# Electronic_load_1_0.net
KiCad netlist of a schematic drawn in Altium Designer
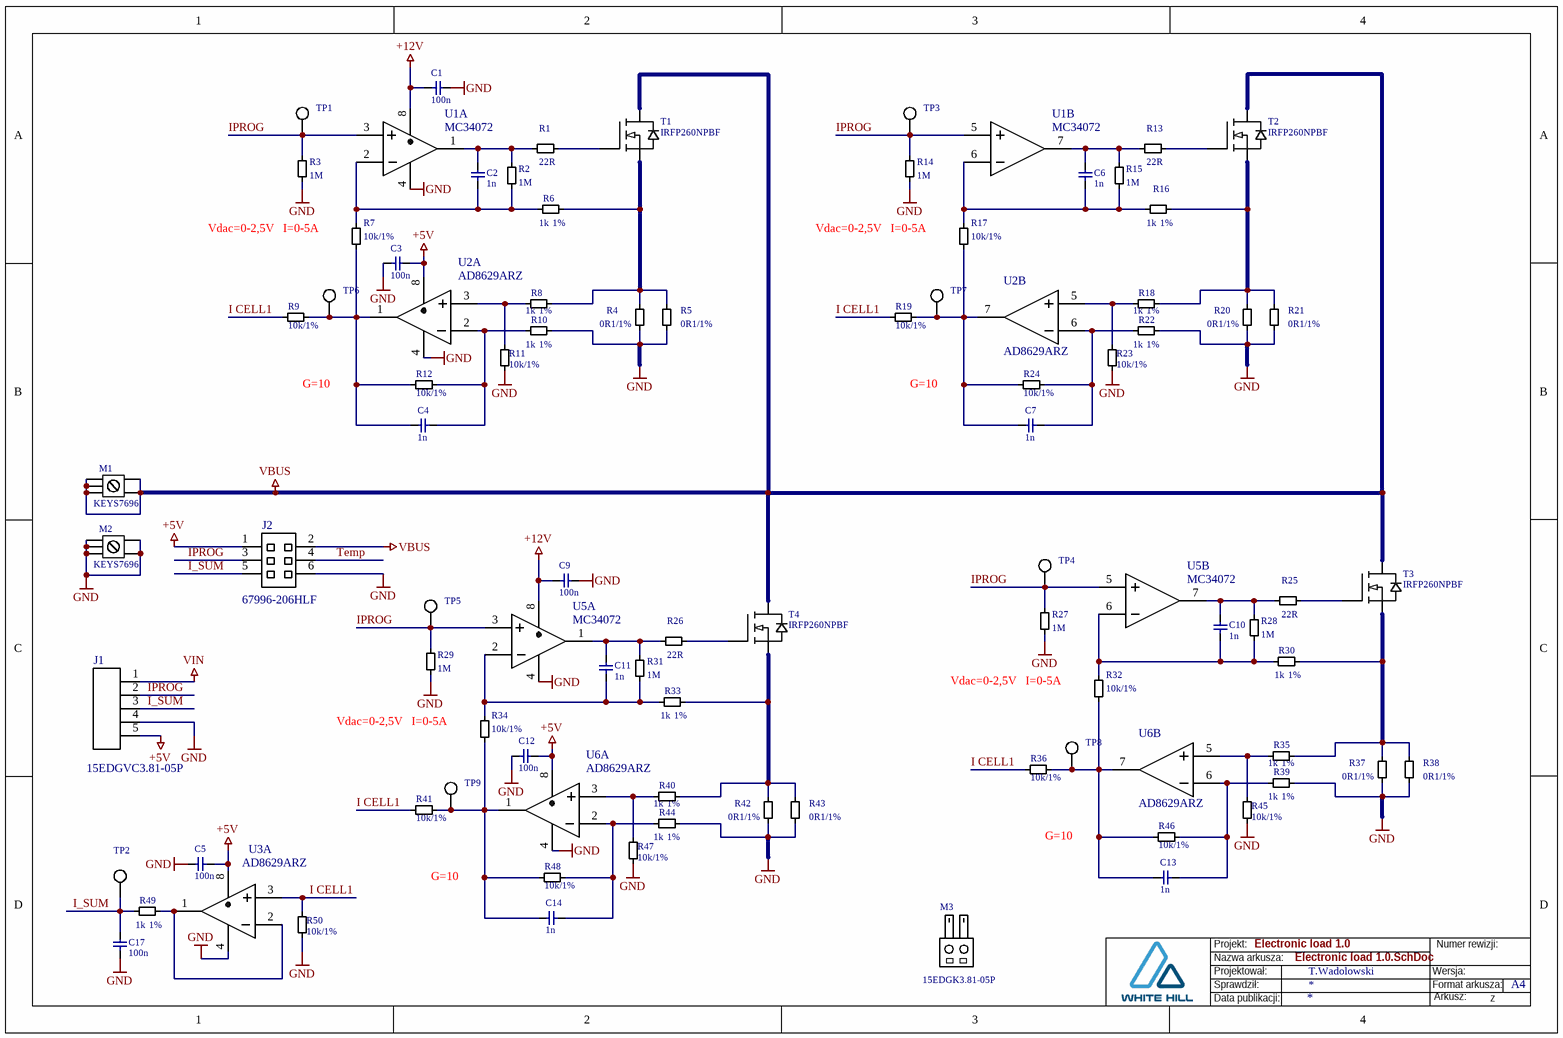
[diagram p0: Electronic load 1.0.SchDoc]

(export (version "E")
  (design (tool "Eeschema 10.0.6"))
  (components
    (comp (ref "C1")
      (value "100n")
      (footprint "C0603")
      (description "Capacitor: ceramic; 100nF; 50V; X7R; ±10%; SMD; 0603; Series: GRM")
      (fields (field (name "MANUFACTURER") "Murata") (field (name "PART NUMBER") "GRM188R71H104KA93D"))
      (libsource (lib "CAPcer") (part "C-013"))
    )
    (comp (ref "C2")
      (value "1n")
      (footprint "C0603")
      (description "Capacitor: ceramic; MLCC; 1nF; 50V; X7R; ±10%; SMD; 0603")
      (fields (field (name "MANUFACTURER") "Vishay") (field (name "PART NUMBER") "VJ0603Y102KXACW1BC"))
      (libsource (lib "CAPcer") (part "C-006"))
    )
    (comp (ref "C3")
      (value "100n")
      (footprint "C0603")
      (description "Capacitor: ceramic; 100nF; 50V; X7R; ±10%; SMD; 0603; Series: GRM")
      (fields (field (name "MANUFACTURER") "Murata") (field (name "PART NUMBER") "GRM188R71H104KA93D"))
      (libsource (lib "CAPcer") (part "C-013"))
    )
    (comp (ref "C4")
      (value "1n")
      (footprint "C0603")
      (description "Capacitor: ceramic; MLCC; 1nF; 50V; X7R; ±10%; SMD; 0603")
      (fields (field (name "MANUFACTURER") "Vishay") (field (name "PART NUMBER") "VJ0603Y102KXACW1BC"))
      (libsource (lib "CAPcer") (part "C-006"))
    )
    (comp (ref "C5")
      (value "100n")
      (footprint "C0603")
      (description "Capacitor: ceramic; 100nF; 50V; X7R; ±10%; SMD; 0603; Series: GRM")
      (fields (field (name "MANUFACTURER") "Murata") (field (name "PART NUMBER") "GRM188R71H104KA93D"))
      (libsource (lib "CAPcer") (part "C-013"))
    )
    (comp (ref "C6")
      (value "1n")
      (footprint "C0603")
      (description "Capacitor: ceramic; MLCC; 1nF; 50V; X7R; ±10%; SMD; 0603")
      (fields (field (name "MANUFACTURER") "Vishay") (field (name "PART NUMBER") "VJ0603Y102KXACW1BC"))
      (libsource (lib "CAPcer") (part "C-006"))
    )
    (comp (ref "C7")
      (value "1n")
      (footprint "C0603")
      (description "Capacitor: ceramic; MLCC; 1nF; 50V; X7R; ±10%; SMD; 0603")
      (fields (field (name "MANUFACTURER") "Vishay") (field (name "PART NUMBER") "VJ0603Y102KXACW1BC"))
      (libsource (lib "CAPcer") (part "C-006"))
    )
    (comp (ref "C9")
      (value "100n")
      (footprint "C0603")
      (description "Capacitor: ceramic; 100nF; 50V; X7R; ±10%; SMD; 0603; Series: GRM")
      (fields (field (name "MANUFACTURER") "Murata") (field (name "PART NUMBER") "GRM188R71H104KA93D"))
      (libsource (lib "CAPcer") (part "C-013"))
    )
    (comp (ref "C10")
      (value "1n")
      (footprint "C0603")
      (description "Capacitor: ceramic; MLCC; 1nF; 50V; X7R; ±10%; SMD; 0603")
      (fields (field (name "MANUFACTURER") "Vishay") (field (name "PART NUMBER") "VJ0603Y102KXACW1BC"))
      (libsource (lib "CAPcer") (part "C-006"))
    )
    (comp (ref "C11")
      (value "1n")
      (footprint "C0603")
      (description "Capacitor: ceramic; MLCC; 1nF; 50V; X7R; ±10%; SMD; 0603")
      (fields (field (name "MANUFACTURER") "Vishay") (field (name "PART NUMBER") "VJ0603Y102KXACW1BC"))
      (libsource (lib "CAPcer") (part "C-006"))
    )
    (comp (ref "C12")
      (value "100n")
      (footprint "C0603")
      (description "Capacitor: ceramic; 100nF; 50V; X7R; ±10%; SMD; 0603; Series: GRM")
      (fields (field (name "MANUFACTURER") "Murata") (field (name "PART NUMBER") "GRM188R71H104KA93D"))
      (libsource (lib "CAPcer") (part "C-013"))
    )
    (comp (ref "C13")
      (value "1n")
      (footprint "C0603")
      (description "Capacitor: ceramic; MLCC; 1nF; 50V; X7R; ±10%; SMD; 0603")
      (fields (field (name "MANUFACTURER") "Vishay") (field (name "PART NUMBER") "VJ0603Y102KXACW1BC"))
      (libsource (lib "CAPcer") (part "C-006"))
    )
    (comp (ref "C14")
      (value "1n")
      (footprint "C0603")
      (description "Capacitor: ceramic; MLCC; 1nF; 50V; X7R; ±10%; SMD; 0603")
      (fields (field (name "MANUFACTURER") "Vishay") (field (name "PART NUMBER") "VJ0603Y102KXACW1BC"))
      (libsource (lib "CAPcer") (part "C-006"))
    )
    (comp (ref "C17")
      (value "100n")
      (footprint "C0603")
      (description "Capacitor: ceramic; 100nF; 50V; X7R; ±10%; SMD; 0603; Series: GRM")
      (fields (field (name "MANUFACTURER") "Murata") (field (name "PART NUMBER") "GRM188R71H104KA93D"))
      (libsource (lib "CAPcer") (part "C-013"))
    )
    (comp (ref "J1")
      (value "15EDGVC3.81-05P")
      (footprint "MCV1,5/5-G3,81")
      (description "Pluggable terminal block; 3.81mm; ways:5; straight; socket; male")
      (fields (field (name "PART NUMBER") "15EDGVC-3.81-05P-14-00A(H)"))
      (libsource (lib "WH") (part "CON5"))
    )
    (comp (ref "J2")
      (value "67996-206HLF")
      (footprint "GP2x3")
      (description "Pin header; pin strips; male;2.54mm; PIN:6; THT")
      (fields (field (name "MANUFACTURER") "Amphenol"))
      (libsource (lib "WH") (part "CON2x3"))
    )
    (comp (ref "M1")
      (value "KEYS7696")
      (footprint "KEY-7696")
      (description "Terminal: screw terminal; THT, screw terminal; silver; 7x5mm")
      (fields (field (name "MANUFACTURER") "Keystone") (field (name "PART NUMBER") "7696"))
      (libsource (lib "WH") (part "M3 pcb"))
    )
    (comp (ref "M2")
      (value "KEYS7696")
      (footprint "KEY-7696")
      (description "Terminal: screw terminal; THT, screw terminal; silver; 7x5mm")
      (fields (field (name "MANUFACTURER") "Keystone") (field (name "PART NUMBER") "7696"))
      (libsource (lib "WH") (part "M3 pcb"))
    )
    (comp (ref "M3")
      (value "15EDGK3.81-05P")
      (description "Pluggable terminal block; 3.81mm; ways:5; straight; plug; female")
      (fields (field (name "PART NUMBER") "15EDGK-3.81-05P-14-00A(H)"))
      (libsource (lib "WH") (part "Wtyk 3,81"))
    )
    (comp (ref "R1")
      (value "22R")
      (footprint "R0603")
      (description "Resistor: thick film; SMD; 0603; 22R; 0.1W; ±5%;")
      (fields (field (name "MANUFACTURER") "Royal Ohm") (field (name "PART NUMBER") "0603SAJ0220T5E"))
      (libsource (lib "Resistors") (part "R-002"))
    )
    (comp (ref "R2")
      (value "1M")
      (footprint "R0603")
      (description "Resistor: thick film; SMD; 0603; 1M; 0.1W; ±5%;")
      (fields (field (name "MANUFACTURER") "Royal Ohm") (field (name "PART NUMBER") "0603SAJ0105T5E"))
      (libsource (lib "Resistors") (part "R-022"))
    )
    (comp (ref "R3")
      (value "1M")
      (footprint "R0603")
      (description "Resistor: thick film; SMD; 0603; 1M; 0.1W; ±5%;")
      (fields (field (name "MANUFACTURER") "Royal Ohm") (field (name "PART NUMBER") "0603SAJ0105T5E"))
      (libsource (lib "Resistors") (part "R-022"))
    )
    (comp (ref "R4")
      (value "0R1/1%")
      (footprint "R2512")
      (description "Rezystor: pomiarowy; SMD; 2512; 100mOhm; 3W; ±1%; 50ppm")
      (fields (field (name "MANUFACTURER") "Viking") (field (name "PART NUMBER") "LPR12FTDRR100"))
      (libsource (lib "") (part "R_2"))
    )
    (comp (ref "R5")
      (value "0R1/1%")
      (footprint "R2512")
      (description "Rezystor: pomiarowy; SMD; 2512; 100mOhm; 3W; ±1%; 50ppm")
      (fields (field (name "MANUFACTURER") "Viking") (field (name "PART NUMBER") "LPR12FTDRR100"))
      (libsource (lib "") (part "R_2"))
    )
    (comp (ref "R6")
      (value "1k")
      (footprint "R0603")
      (description "Resistor: thick film; SMD; 0603; 1k; 0.1W; ±1%")
      (fields
        (field (name "MANUFACTURER") "Royal Ohm")
        (field (name "PART NUMBER") "0603SAF1001T5E")
        (field (name "TOLERANCE") "1%")
      )
      (libsource (lib "Resistors") (part "R-035"))
    )
    (comp (ref "R7")
      (value "10k/1%")
      (footprint "R0603")
      (description "Rezystor: thick film; SMD; 0603; 10kOhm; 0,1W; ±1%; -55÷155°C")
      (fields (field (name "MANUFACTURER") "VISHAY") (field (name "PART NUMBER") "CRCW060310K0FKTABC"))
      (libsource (lib "DGI") (part "R"))
    )
    (comp (ref "R8")
      (value "1k")
      (footprint "R0603")
      (description "Resistor: thick film; SMD; 0603; 1k; 0.1W; ±1%")
      (fields
        (field (name "MANUFACTURER") "Royal Ohm")
        (field (name "PART NUMBER") "0603SAF1001T5E")
        (field (name "TOLERANCE") "1%")
      )
      (libsource (lib "Resistors") (part "R-035"))
    )
    (comp (ref "R9")
      (value "10k/1%")
      (footprint "R0603")
      (description "Rezystor: thick film; SMD; 0603; 10kOhm; 0,1W; ±1%; -55÷155°C")
      (fields (field (name "MANUFACTURER") "VISHAY") (field (name "PART NUMBER") "CRCW060310K0FKTABC"))
      (libsource (lib "") (part "R_1"))
    )
    (comp (ref "R10")
      (value "1k")
      (footprint "R0603")
      (description "Resistor: thick film; SMD; 0603; 1k; 0.1W; ±1%")
      (fields
        (field (name "MANUFACTURER") "Royal Ohm")
        (field (name "PART NUMBER") "0603SAF1001T5E")
        (field (name "TOLERANCE") "1%")
      )
      (libsource (lib "Resistors") (part "R-035"))
    )
    (comp (ref "R11")
      (value "10k/1%")
      (footprint "R0603")
      (description "Rezystor: thick film; SMD; 0603; 10kOhm; 0,1W; ±1%; -55÷155°C")
      (fields (field (name "MANUFACTURER") "VISHAY") (field (name "PART NUMBER") "CRCW060310K0FKTABC"))
      (libsource (lib "") (part "R_2"))
    )
    (comp (ref "R12")
      (value "10k/1%")
      (footprint "R0603")
      (description "Rezystor: thick film; SMD; 0603; 10kOhm; 0,1W; ±1%; -55÷155°C")
      (fields (field (name "MANUFACTURER") "VISHAY") (field (name "PART NUMBER") "CRCW060310K0FKTABC"))
      (libsource (lib "") (part "R_3"))
    )
    (comp (ref "R13")
      (value "22R")
      (footprint "R0603")
      (description "Resistor: thick film; SMD; 0603; 22R; 0.1W; ±5%;")
      (fields (field (name "MANUFACTURER") "Royal Ohm") (field (name "PART NUMBER") "0603SAJ0220T5E"))
      (libsource (lib "Resistors") (part "R-002"))
    )
    (comp (ref "R14")
      (value "1M")
      (footprint "R0603")
      (description "Resistor: thick film; SMD; 0603; 1M; 0.1W; ±5%;")
      (fields (field (name "MANUFACTURER") "Royal Ohm") (field (name "PART NUMBER") "0603SAJ0105T5E"))
      (libsource (lib "Resistors") (part "R-022"))
    )
    (comp (ref "R15")
      (value "1M")
      (footprint "R0603")
      (description "Resistor: thick film; SMD; 0603; 1M; 0.1W; ±5%;")
      (fields (field (name "MANUFACTURER") "Royal Ohm") (field (name "PART NUMBER") "0603SAJ0105T5E"))
      (libsource (lib "Resistors") (part "R-022"))
    )
    (comp (ref "R16")
      (value "1k")
      (footprint "R0603")
      (description "Resistor: thick film; SMD; 0603; 1k; 0.1W; ±1%")
      (fields
        (field (name "MANUFACTURER") "Royal Ohm")
        (field (name "PART NUMBER") "0603SAF1001T5E")
        (field (name "TOLERANCE") "1%")
      )
      (libsource (lib "Resistors") (part "R-035"))
    )
    (comp (ref "R17")
      (value "10k/1%")
      (footprint "R0603")
      (description "Rezystor: thick film; SMD; 0603; 10kOhm; 0,1W; ±1%; -55÷155°C")
      (fields (field (name "MANUFACTURER") "VISHAY") (field (name "PART NUMBER") "CRCW060310K0FKTABC"))
      (libsource (lib "DGI") (part "R"))
    )
    (comp (ref "R18")
      (value "1k")
      (footprint "R0603")
      (description "Resistor: thick film; SMD; 0603; 1k; 0.1W; ±1%")
      (fields
        (field (name "MANUFACTURER") "Royal Ohm")
        (field (name "PART NUMBER") "0603SAF1001T5E")
        (field (name "TOLERANCE") "1%")
      )
      (libsource (lib "Resistors") (part "R-035"))
    )
    (comp (ref "R19")
      (value "10k/1%")
      (footprint "R0603")
      (description "Rezystor: thick film; SMD; 0603; 10kOhm; 0,1W; ±1%; -55÷155°C")
      (fields (field (name "MANUFACTURER") "VISHAY") (field (name "PART NUMBER") "CRCW060310K0FKTABC"))
      (libsource (lib "") (part "R_1"))
    )
    (comp (ref "R20")
      (value "0R1/1%")
      (footprint "R2512")
      (description "Rezystor: pomiarowy; SMD; 2512; 100mOhm; 3W; ±1%; 50ppm")
      (fields (field (name "MANUFACTURER") "Viking") (field (name "PART NUMBER") "LPR12FTDRR100"))
      (libsource (lib "") (part "R_2"))
    )
    (comp (ref "R21")
      (value "0R1/1%")
      (footprint "R2512")
      (description "Rezystor: pomiarowy; SMD; 2512; 100mOhm; 3W; ±1%; 50ppm")
      (fields (field (name "MANUFACTURER") "Viking") (field (name "PART NUMBER") "LPR12FTDRR100"))
      (libsource (lib "") (part "R_2"))
    )
    (comp (ref "R22")
      (value "1k")
      (footprint "R0603")
      (description "Resistor: thick film; SMD; 0603; 1k; 0.1W; ±1%")
      (fields
        (field (name "MANUFACTURER") "Royal Ohm")
        (field (name "PART NUMBER") "0603SAF1001T5E")
        (field (name "TOLERANCE") "1%")
      )
      (libsource (lib "Resistors") (part "R-035"))
    )
    (comp (ref "R23")
      (value "10k/1%")
      (footprint "R0603")
      (description "Rezystor: thick film; SMD; 0603; 10kOhm; 0,1W; ±1%; -55÷155°C")
      (fields (field (name "MANUFACTURER") "VISHAY") (field (name "PART NUMBER") "CRCW060310K0FKTABC"))
      (libsource (lib "") (part "R_2"))
    )
    (comp (ref "R24")
      (value "10k/1%")
      (footprint "R0603")
      (description "Rezystor: thick film; SMD; 0603; 10kOhm; 0,1W; ±1%; -55÷155°C")
      (fields (field (name "MANUFACTURER") "VISHAY") (field (name "PART NUMBER") "CRCW060310K0FKTABC"))
      (libsource (lib "") (part "R_3"))
    )
    (comp (ref "R25")
      (value "22R")
      (footprint "R0603")
      (description "Resistor: thick film; SMD; 0603; 22R; 0.1W; ±5%;")
      (fields (field (name "MANUFACTURER") "Royal Ohm") (field (name "PART NUMBER") "0603SAJ0220T5E"))
      (libsource (lib "Resistors") (part "R-002"))
    )
    (comp (ref "R26")
      (value "22R")
      (footprint "R0603")
      (description "Resistor: thick film; SMD; 0603; 22R; 0.1W; ±5%;")
      (fields (field (name "MANUFACTURER") "Royal Ohm") (field (name "PART NUMBER") "0603SAJ0220T5E"))
      (libsource (lib "Resistors") (part "R-002"))
    )
    (comp (ref "R27")
      (value "1M")
      (footprint "R0603")
      (description "Resistor: thick film; SMD; 0603; 1M; 0.1W; ±5%;")
      (fields (field (name "MANUFACTURER") "Royal Ohm") (field (name "PART NUMBER") "0603SAJ0105T5E"))
      (libsource (lib "Resistors") (part "R-022"))
    )
    (comp (ref "R28")
      (value "1M")
      (footprint "R0603")
      (description "Resistor: thick film; SMD; 0603; 1M; 0.1W; ±5%;")
      (fields (field (name "MANUFACTURER") "Royal Ohm") (field (name "PART NUMBER") "0603SAJ0105T5E"))
      (libsource (lib "Resistors") (part "R-022"))
    )
    (comp (ref "R29")
      (value "1M")
      (footprint "R0603")
      (description "Resistor: thick film; SMD; 0603; 1M; 0.1W; ±5%;")
      (fields (field (name "MANUFACTURER") "Royal Ohm") (field (name "PART NUMBER") "0603SAJ0105T5E"))
      (libsource (lib "Resistors") (part "R-022"))
    )
    (comp (ref "R30")
      (value "1k")
      (footprint "R0603")
      (description "Resistor: thick film; SMD; 0603; 1k; 0.1W; ±1%")
      (fields
        (field (name "MANUFACTURER") "Royal Ohm")
        (field (name "PART NUMBER") "0603SAF1001T5E")
        (field (name "TOLERANCE") "1%")
      )
      (libsource (lib "Resistors") (part "R-035"))
    )
    (comp (ref "R31")
      (value "1M")
      (footprint "R0603")
      (description "Resistor: thick film; SMD; 0603; 1M; 0.1W; ±5%;")
      (fields (field (name "MANUFACTURER") "Royal Ohm") (field (name "PART NUMBER") "0603SAJ0105T5E"))
      (libsource (lib "Resistors") (part "R-022"))
    )
    (comp (ref "R32")
      (value "10k/1%")
      (footprint "R0603")
      (description "Rezystor: thick film; SMD; 0603; 10kOhm; 0,1W; ±1%; -55÷155°C")
      (fields (field (name "MANUFACTURER") "VISHAY") (field (name "PART NUMBER") "CRCW060310K0FKTABC"))
      (libsource (lib "DGI") (part "R"))
    )
    (comp (ref "R33")
      (value "1k")
      (footprint "R0603")
      (description "Resistor: thick film; SMD; 0603; 1k; 0.1W; ±1%")
      (fields
        (field (name "MANUFACTURER") "Royal Ohm")
        (field (name "PART NUMBER") "0603SAF1001T5E")
        (field (name "TOLERANCE") "1%")
      )
      (libsource (lib "Resistors") (part "R-035"))
    )
    (comp (ref "R34")
      (value "10k/1%")
      (footprint "R0603")
      (description "Rezystor: thick film; SMD; 0603; 10kOhm; 0,1W; ±1%; -55÷155°C")
      (fields (field (name "MANUFACTURER") "VISHAY") (field (name "PART NUMBER") "CRCW060310K0FKTABC"))
      (libsource (lib "DGI") (part "R"))
    )
    (comp (ref "R35")
      (value "1k")
      (footprint "R0603")
      (description "Resistor: thick film; SMD; 0603; 1k; 0.1W; ±1%")
      (fields
        (field (name "MANUFACTURER") "Royal Ohm")
        (field (name "PART NUMBER") "0603SAF1001T5E")
        (field (name "TOLERANCE") "1%")
      )
      (libsource (lib "Resistors") (part "R-035"))
    )
    (comp (ref "R36")
      (value "10k/1%")
      (footprint "R0603")
      (description "Rezystor: thick film; SMD; 0603; 10kOhm; 0,1W; ±1%; -55÷155°C")
      (fields (field (name "MANUFACTURER") "VISHAY") (field (name "PART NUMBER") "CRCW060310K0FKTABC"))
      (libsource (lib "") (part "R_1"))
    )
    (comp (ref "R37")
      (value "0R1/1%")
      (footprint "R2512")
      (description "Rezystor: pomiarowy; SMD; 2512; 100mOhm; 3W; ±1%; 50ppm")
      (fields (field (name "MANUFACTURER") "Viking") (field (name "PART NUMBER") "LPR12FTDRR100"))
      (libsource (lib "") (part "R_2"))
    )
    (comp (ref "R38")
      (value "0R1/1%")
      (footprint "R2512")
      (description "Rezystor: pomiarowy; SMD; 2512; 100mOhm; 3W; ±1%; 50ppm")
      (fields (field (name "MANUFACTURER") "Viking") (field (name "PART NUMBER") "LPR12FTDRR100"))
      (libsource (lib "") (part "R_2"))
    )
    (comp (ref "R39")
      (value "1k")
      (footprint "R0603")
      (description "Resistor: thick film; SMD; 0603; 1k; 0.1W; ±1%")
      (fields
        (field (name "MANUFACTURER") "Royal Ohm")
        (field (name "PART NUMBER") "0603SAF1001T5E")
        (field (name "TOLERANCE") "1%")
      )
      (libsource (lib "Resistors") (part "R-035"))
    )
    (comp (ref "R40")
      (value "1k")
      (footprint "R0603")
      (description "Resistor: thick film; SMD; 0603; 1k; 0.1W; ±1%")
      (fields
        (field (name "MANUFACTURER") "Royal Ohm")
        (field (name "PART NUMBER") "0603SAF1001T5E")
        (field (name "TOLERANCE") "1%")
      )
      (libsource (lib "Resistors") (part "R-035"))
    )
    (comp (ref "R41")
      (value "10k/1%")
      (footprint "R0603")
      (description "Rezystor: thick film; SMD; 0603; 10kOhm; 0,1W; ±1%; -55÷155°C")
      (fields (field (name "MANUFACTURER") "VISHAY") (field (name "PART NUMBER") "CRCW060310K0FKTABC"))
      (libsource (lib "") (part "R_1"))
    )
    (comp (ref "R42")
      (value "0R1/1%")
      (footprint "R2512")
      (description "Rezystor: pomiarowy; SMD; 2512; 100mOhm; 3W; ±1%; 50ppm")
      (fields (field (name "MANUFACTURER") "Viking") (field (name "PART NUMBER") "LPR12FTDRR100"))
      (libsource (lib "") (part "R_2"))
    )
    (comp (ref "R43")
      (value "0R1/1%")
      (footprint "R2512")
      (description "Rezystor: pomiarowy; SMD; 2512; 100mOhm; 3W; ±1%; 50ppm")
      (fields (field (name "MANUFACTURER") "Viking") (field (name "PART NUMBER") "LPR12FTDRR100"))
      (libsource (lib "") (part "R_2"))
    )
    (comp (ref "R44")
      (value "1k")
      (footprint "R0603")
      (description "Resistor: thick film; SMD; 0603; 1k; 0.1W; ±1%")
      (fields
        (field (name "MANUFACTURER") "Royal Ohm")
        (field (name "PART NUMBER") "0603SAF1001T5E")
        (field (name "TOLERANCE") "1%")
      )
      (libsource (lib "Resistors") (part "R-035"))
    )
    (comp (ref "R45")
      (value "10k/1%")
      (footprint "R0603")
      (description "Rezystor: thick film; SMD; 0603; 10kOhm; 0,1W; ±1%; -55÷155°C")
      (fields (field (name "MANUFACTURER") "VISHAY") (field (name "PART NUMBER") "CRCW060310K0FKTABC"))
      (libsource (lib "") (part "R_2"))
    )
    (comp (ref "R46")
      (value "10k/1%")
      (footprint "R0603")
      (description "Rezystor: thick film; SMD; 0603; 10kOhm; 0,1W; ±1%; -55÷155°C")
      (fields (field (name "MANUFACTURER") "VISHAY") (field (name "PART NUMBER") "CRCW060310K0FKTABC"))
      (libsource (lib "") (part "R_3"))
    )
    (comp (ref "R47")
      (value "10k/1%")
      (footprint "R0603")
      (description "Rezystor: thick film; SMD; 0603; 10kOhm; 0,1W; ±1%; -55÷155°C")
      (fields (field (name "MANUFACTURER") "VISHAY") (field (name "PART NUMBER") "CRCW060310K0FKTABC"))
      (libsource (lib "") (part "R_2"))
    )
    (comp (ref "R48")
      (value "10k/1%")
      (footprint "R0603")
      (description "Rezystor: thick film; SMD; 0603; 10kOhm; 0,1W; ±1%; -55÷155°C")
      (fields (field (name "MANUFACTURER") "VISHAY") (field (name "PART NUMBER") "CRCW060310K0FKTABC"))
      (libsource (lib "") (part "R_3"))
    )
    (comp (ref "R49")
      (value "1k")
      (footprint "R0603")
      (description "Resistor: thick film; SMD; 0603; 1k; 0.1W; ±1%")
      (fields
        (field (name "MANUFACTURER") "Royal Ohm")
        (field (name "PART NUMBER") "0603SAF1001T5E")
        (field (name "TOLERANCE") "1%")
      )
      (libsource (lib "Resistors") (part "R-035"))
    )
    (comp (ref "R50")
      (value "10k/1%")
      (footprint "R0603")
      (description "Rezystor: thick film; SMD; 0603; 10kOhm; 0,1W; ±1%; -55÷155°C")
      (fields (field (name "MANUFACTURER") "VISHAY") (field (name "PART NUMBER") "CRCW060310K0FKTABC"))
      (libsource (lib "DGI") (part "R"))
    )
    (comp (ref "T1")
      (value "IRFP260NPBF")
      (footprint "TO-247-HOR")
      (description "Tranzystor: N-MOSFET; unipolarny; HEXFET; 200V; 35A; 300W; TO247AC")
      (fields (field (name "MANUFACTURER") "Infineon"))
      (libsource (lib "WH") (part "IRFP260NPBF"))
    )
    (comp (ref "T2")
      (value "IRFP260NPBF")
      (footprint "TO-247-HOR")
      (description "Tranzystor: N-MOSFET; unipolarny; HEXFET; 200V; 35A; 300W; TO247AC")
      (fields (field (name "MANUFACTURER") "Infineon"))
      (libsource (lib "WH") (part "IRFP260NPBF"))
    )
    (comp (ref "T3")
      (value "IRFP260NPBF")
      (footprint "TO-247-HOR")
      (description "Tranzystor: N-MOSFET; unipolarny; HEXFET; 200V; 35A; 300W; TO247AC")
      (fields (field (name "MANUFACTURER") "Infineon"))
      (libsource (lib "WH") (part "IRFP260NPBF"))
    )
    (comp (ref "T4")
      (value "IRFP260NPBF")
      (footprint "TO-247-HOR")
      (description "Tranzystor: N-MOSFET; unipolarny; HEXFET; 200V; 35A; 300W; TO247AC")
      (fields (field (name "MANUFACTURER") "Infineon"))
      (libsource (lib "WH") (part "IRFP260NPBF"))
    )
    (comp (ref "TP1")
      (value "TP")
      (footprint "TP")
      (description "Test point")
      (libsource (lib "DGI") (part "TP"))
    )
    (comp (ref "TP2")
      (value "TP")
      (footprint "TP")
      (description "Test point")
      (libsource (lib "DGI") (part "TP"))
    )
    (comp (ref "TP3")
      (value "TP")
      (footprint "TP")
      (description "Test point")
      (libsource (lib "DGI") (part "TP"))
    )
    (comp (ref "TP4")
      (value "TP")
      (footprint "TP")
      (description "Test point")
      (libsource (lib "DGI") (part "TP"))
    )
    (comp (ref "TP5")
      (value "TP")
      (footprint "TP")
      (description "Test point")
      (libsource (lib "DGI") (part "TP"))
    )
    (comp (ref "TP6")
      (value "TP")
      (footprint "TP")
      (description "Test point")
      (libsource (lib "DGI") (part "TP"))
    )
    (comp (ref "TP7")
      (value "TP")
      (footprint "TP")
      (description "Test point")
      (libsource (lib "DGI") (part "TP"))
    )
    (comp (ref "TP8")
      (value "TP")
      (footprint "TP")
      (description "Test point")
      (libsource (lib "DGI") (part "TP"))
    )
    (comp (ref "TP9")
      (value "TP")
      (footprint "TP")
      (description "Test point")
      (libsource (lib "DGI") (part "TP"))
    )
    (comp (ref "U1")
      (value "MC34072")
      (footprint "SO-8")
      (description "Operational Amplifier Dual;4,5MHz,3-44V,SOIC-8")
      (fields (field (name "MANUFACTURER") "TI") (field (name "PART NUMBER") "MC34072ADG"))
      (libsource (lib "WH") (part "MC34072"))
    )
    (comp (ref "U2")
      (value "AD8629ARZ")
      (footprint "SO-8")
      (description "Zero-Drift, Single-Supply, Rail-to-Rail  Input/Output Operational Amplifier")
      (fields (field (name "MANUFACTURER") "Analog Devices"))
      (libsource (lib "WH") (part "AD8629"))
    )
    (comp (ref "U3")
      (value "AD8629ARZ")
      (footprint "SO-8")
      (description "Zero-Drift, Single-Supply, Rail-to-Rail  Input/Output Operational Amplifier")
      (fields (field (name "MANUFACTURER") "Analog Devices"))
      (libsource (lib "WH") (part "AD8629"))
    )
    (comp (ref "U5")
      (value "MC34072")
      (footprint "SO-8")
      (description "Operational Amplifier Dual;4,5MHz,3-44V,SOIC-8")
      (fields (field (name "MANUFACTURER") "TI") (field (name "PART NUMBER") "MC34072ADG"))
      (libsource (lib "WH") (part "MC34072"))
    )
    (comp (ref "U6")
      (value "AD8629ARZ")
      (footprint "SO-8")
      (description "Zero-Drift, Single-Supply, Rail-to-Rail  Input/Output Operational Amplifier")
      (fields (field (name "MANUFACTURER") "Analog Devices"))
      (libsource (lib "WH") (part "AD8629"))
    )
  )
  (nets
    (net (code "1") (name "+5V") (class "Default")
      (node (ref "C12") (pin "1") (pinfunction "1_1") (pintype "passive"))
      (node (ref "C3") (pin "1") (pinfunction "1_1") (pintype "passive"))
      (node (ref "C5") (pin "2") (pinfunction "2_2") (pintype "passive"))
      (node (ref "J1") (pin "5") (pinfunction "5_5") (pintype "passive"))
      (node (ref "J2") (pin "1") (pinfunction "1_1") (pintype "passive"))
      (node (ref "U2") (pin "8") (pinfunction "V+_8") (pintype "passive"))
      (node (ref "U3") (pin "8") (pinfunction "V+_8") (pintype "passive"))
      (node (ref "U6") (pin "8") (pinfunction "V+_8") (pintype "passive"))
    )
    (net (code "2") (name "+12V") (class "Default")
      (node (ref "C1") (pin "2") (pinfunction "2_2") (pintype "passive"))
      (node (ref "C9") (pin "2") (pinfunction "2_2") (pintype "passive"))
      (node (ref "U1") (pin "8") (pinfunction "V+_8") (pintype "passive"))
      (node (ref "U5") (pin "8") (pinfunction "V+_8") (pintype "passive"))
    )
    (net (code "3") (name "/I CELL1") (class "Default")
      (node (ref "R19") (pin "1") (pinfunction "TOP_1") (pintype "passive"))
      (node (ref "R36") (pin "1") (pinfunction "TOP_1") (pintype "passive"))
      (node (ref "R41") (pin "1") (pinfunction "TOP_1") (pintype "passive"))
      (node (ref "R50") (pin "2") (pinfunction "BOT_2") (pintype "passive"))
      (node (ref "R9") (pin "1") (pinfunction "TOP_1") (pintype "passive"))
      (node (ref "U3") (pin "3") (pinfunction "1IN+_3") (pintype "passive"))
    )
    (net (code "4") (name "/IPROG") (class "Default")
      (node (ref "J1") (pin "2") (pinfunction "2_2") (pintype "passive"))
      (node (ref "J2") (pin "3") (pinfunction "3_3") (pintype "passive"))
      (node (ref "R14") (pin "2") (pinfunction "BOT_2") (pintype "passive"))
      (node (ref "R27") (pin "2") (pinfunction "BOT_2") (pintype "passive"))
      (node (ref "R29") (pin "2") (pinfunction "BOT_2") (pintype "passive"))
      (node (ref "R3") (pin "2") (pinfunction "BOT_2") (pintype "passive"))
      (node (ref "TP1") (pin "1") (pinfunction "1_1") (pintype "passive"))
      (node (ref "TP3") (pin "1") (pinfunction "1_1") (pintype "passive"))
      (node (ref "TP4") (pin "1") (pinfunction "1_1") (pintype "passive"))
      (node (ref "TP5") (pin "1") (pinfunction "1_1") (pintype "passive"))
      (node (ref "U1") (pin "3") (pinfunction "1IN+_3") (pintype "passive"))
      (node (ref "U1") (pin "5") (pinfunction "2IN+_5") (pintype "passive"))
      (node (ref "U5") (pin "3") (pinfunction "1IN+_3") (pintype "passive"))
      (node (ref "U5") (pin "5") (pinfunction "2IN+_5") (pintype "passive"))
    )
    (net (code "5") (name "/I_SUM") (class "Default")
      (node (ref "C17") (pin "1") (pinfunction "1_1") (pintype "passive"))
      (node (ref "J1") (pin "3") (pinfunction "3_3") (pintype "passive"))
      (node (ref "J2") (pin "5") (pinfunction "5_5") (pintype "passive"))
      (node (ref "R49") (pin "2") (pinfunction "BOT_2") (pintype "passive"))
      (node (ref "TP2") (pin "1") (pinfunction "1_1") (pintype "passive"))
    )
    (net (code "6") (name "/Temp") (class "Default")
      (node (ref "J2") (pin "4") (pinfunction "4_4") (pintype "passive"))
    )
    (net (code "7") (name "GND") (class "Default")
      (node (ref "C1") (pin "1") (pinfunction "1_1") (pintype "passive"))
      (node (ref "C12") (pin "2") (pinfunction "2_2") (pintype "passive"))
      (node (ref "C17") (pin "2") (pinfunction "2_2") (pintype "passive"))
      (node (ref "C3") (pin "2") (pinfunction "2_2") (pintype "passive"))
      (node (ref "C5") (pin "1") (pinfunction "1_1") (pintype "passive"))
      (node (ref "C9") (pin "1") (pinfunction "1_1") (pintype "passive"))
      (node (ref "J1") (pin "4") (pinfunction "4_4") (pintype "passive"))
      (node (ref "J2") (pin "6") (pinfunction "6_6") (pintype "passive"))
      (node (ref "M2") (pin "1") (pinfunction "1_1") (pintype "passive"))
      (node (ref "M2") (pin "2") (pinfunction "2_2") (pintype "passive"))
      (node (ref "M2") (pin "3") (pinfunction "3_3") (pintype "passive"))
      (node (ref "M2") (pin "4") (pinfunction "4_4") (pintype "passive"))
      (node (ref "M2") (pin "5") (pinfunction "5_5") (pintype "passive"))
      (node (ref "R10") (pin "1") (pinfunction "TOP_1") (pintype "passive"))
      (node (ref "R11") (pin "2") (pinfunction "BOT_2") (pintype "passive"))
      (node (ref "R14") (pin "1") (pinfunction "TOP_1") (pintype "passive"))
      (node (ref "R20") (pin "2") (pinfunction "BOT_2") (pintype "passive"))
      (node (ref "R21") (pin "2") (pinfunction "BOT_2") (pintype "passive"))
      (node (ref "R22") (pin "1") (pinfunction "TOP_1") (pintype "passive"))
      (node (ref "R23") (pin "2") (pinfunction "BOT_2") (pintype "passive"))
      (node (ref "R27") (pin "1") (pinfunction "TOP_1") (pintype "passive"))
      (node (ref "R29") (pin "1") (pinfunction "TOP_1") (pintype "passive"))
      (node (ref "R3") (pin "1") (pinfunction "TOP_1") (pintype "passive"))
      (node (ref "R37") (pin "2") (pinfunction "BOT_2") (pintype "passive"))
      (node (ref "R38") (pin "2") (pinfunction "BOT_2") (pintype "passive"))
      (node (ref "R39") (pin "1") (pinfunction "TOP_1") (pintype "passive"))
      (node (ref "R4") (pin "2") (pinfunction "BOT_2") (pintype "passive"))
      (node (ref "R42") (pin "2") (pinfunction "BOT_2") (pintype "passive"))
      (node (ref "R43") (pin "2") (pinfunction "BOT_2") (pintype "passive"))
      (node (ref "R44") (pin "1") (pinfunction "TOP_1") (pintype "passive"))
      (node (ref "R45") (pin "2") (pinfunction "BOT_2") (pintype "passive"))
      (node (ref "R47") (pin "2") (pinfunction "BOT_2") (pintype "passive"))
      (node (ref "R5") (pin "2") (pinfunction "BOT_2") (pintype "passive"))
      (node (ref "R50") (pin "1") (pinfunction "TOP_1") (pintype "passive"))
      (node (ref "U1") (pin "4") (pinfunction "V-_4") (pintype "passive"))
      (node (ref "U2") (pin "4") (pinfunction "V-_4") (pintype "passive"))
      (node (ref "U3") (pin "4") (pinfunction "V-_4") (pintype "passive"))
      (node (ref "U5") (pin "4") (pinfunction "V-_4") (pintype "passive"))
      (node (ref "U6") (pin "4") (pinfunction "V-_4") (pintype "passive"))
    )
    (net (code "8") (name "Net-(R1-BOT)") (class "Default")
      (node (ref "R1") (pin "2") (pinfunction "BOT_2") (pintype "passive"))
      (node (ref "T1") (pin "1") (pinfunction "G_1") (pintype "passive"))
    )
    (net (code "9") (name "Net-(R1-TOP)") (class "Default")
      (node (ref "C2") (pin "1") (pinfunction "1_1") (pintype "passive"))
      (node (ref "R1") (pin "1") (pinfunction "TOP_1") (pintype "passive"))
      (node (ref "R2") (pin "2") (pinfunction "BOT_2") (pintype "passive"))
      (node (ref "U1") (pin "1") (pinfunction "1OUT_1") (pintype "passive"))
    )
    (net (code "10") (name "Net-(R2-TOP)") (class "Default")
      (node (ref "C2") (pin "2") (pinfunction "2_2") (pintype "passive"))
      (node (ref "R2") (pin "1") (pinfunction "TOP_1") (pintype "passive"))
      (node (ref "R6") (pin "2") (pinfunction "BOT_2") (pintype "passive"))
      (node (ref "R7") (pin "2") (pinfunction "BOT_2") (pintype "passive"))
      (node (ref "U1") (pin "2") (pinfunction "1IN-_2") (pintype "passive"))
    )
    (net (code "11") (name "Net-(R4-TOP)") (class "Default")
      (node (ref "R4") (pin "1") (pinfunction "TOP_1") (pintype "passive"))
      (node (ref "R5") (pin "1") (pinfunction "TOP_1") (pintype "passive"))
      (node (ref "R6") (pin "1") (pinfunction "TOP_1") (pintype "passive"))
      (node (ref "R8") (pin "1") (pinfunction "TOP_1") (pintype "passive"))
      (node (ref "T1") (pin "3") (pinfunction "S_3") (pintype "passive"))
    )
    (net (code "12") (name "Net-(R10-BOT)") (class "Default")
      (node (ref "C4") (pin "2") (pinfunction "2_2") (pintype "passive"))
      (node (ref "R10") (pin "2") (pinfunction "BOT_2") (pintype "passive"))
      (node (ref "R12") (pin "1") (pinfunction "TOP_1") (pintype "passive"))
      (node (ref "U2") (pin "2") (pinfunction "1IN-_2") (pintype "passive"))
    )
    (net (code "13") (name "Net-(R11-TOP)") (class "Default")
      (node (ref "R11") (pin "1") (pinfunction "TOP_1") (pintype "passive"))
      (node (ref "R8") (pin "2") (pinfunction "BOT_2") (pintype "passive"))
      (node (ref "U2") (pin "3") (pinfunction "1IN+_3") (pintype "passive"))
    )
    (net (code "14") (name "Net-(R12-BOT)") (class "Default")
      (node (ref "C4") (pin "1") (pinfunction "1_1") (pintype "passive"))
      (node (ref "R12") (pin "2") (pinfunction "BOT_2") (pintype "passive"))
      (node (ref "R7") (pin "1") (pinfunction "TOP_1") (pintype "passive"))
      (node (ref "R9") (pin "2") (pinfunction "BOT_2") (pintype "passive"))
      (node (ref "TP6") (pin "1") (pinfunction "1_1") (pintype "passive"))
      (node (ref "U2") (pin "1") (pinfunction "1OUT_1") (pintype "passive"))
    )
    (net (code "15") (name "Net-(R13-BOT)") (class "Default")
      (node (ref "R13") (pin "2") (pinfunction "BOT_2") (pintype "passive"))
      (node (ref "T2") (pin "1") (pinfunction "G_1") (pintype "passive"))
    )
    (net (code "16") (name "Net-(R13-TOP)") (class "Default")
      (node (ref "C6") (pin "1") (pinfunction "1_1") (pintype "passive"))
      (node (ref "R13") (pin "1") (pinfunction "TOP_1") (pintype "passive"))
      (node (ref "R15") (pin "2") (pinfunction "BOT_2") (pintype "passive"))
      (node (ref "U1") (pin "7") (pinfunction "2OUT_7") (pintype "passive"))
    )
    (net (code "17") (name "Net-(R15-TOP)") (class "Default")
      (node (ref "C6") (pin "2") (pinfunction "2_2") (pintype "passive"))
      (node (ref "R15") (pin "1") (pinfunction "TOP_1") (pintype "passive"))
      (node (ref "R16") (pin "2") (pinfunction "BOT_2") (pintype "passive"))
      (node (ref "R17") (pin "2") (pinfunction "BOT_2") (pintype "passive"))
      (node (ref "U1") (pin "6") (pinfunction "2IN-_6") (pintype "passive"))
    )
    (net (code "18") (name "Net-(R16-TOP)") (class "Default")
      (node (ref "R16") (pin "1") (pinfunction "TOP_1") (pintype "passive"))
      (node (ref "R18") (pin "1") (pinfunction "TOP_1") (pintype "passive"))
      (node (ref "R20") (pin "1") (pinfunction "TOP_1") (pintype "passive"))
      (node (ref "R21") (pin "1") (pinfunction "TOP_1") (pintype "passive"))
      (node (ref "T2") (pin "3") (pinfunction "S_3") (pintype "passive"))
    )
    (net (code "19") (name "Net-(R17-TOP)") (class "Default")
      (node (ref "C7") (pin "1") (pinfunction "1_1") (pintype "passive"))
      (node (ref "R17") (pin "1") (pinfunction "TOP_1") (pintype "passive"))
      (node (ref "R19") (pin "2") (pinfunction "BOT_2") (pintype "passive"))
      (node (ref "R24") (pin "2") (pinfunction "BOT_2") (pintype "passive"))
      (node (ref "TP7") (pin "1") (pinfunction "1_1") (pintype "passive"))
      (node (ref "U2") (pin "7") (pinfunction "2OUT_7") (pintype "passive"))
    )
    (net (code "20") (name "Net-(R18-BOT)") (class "Default")
      (node (ref "R18") (pin "2") (pinfunction "BOT_2") (pintype "passive"))
      (node (ref "R23") (pin "1") (pinfunction "TOP_1") (pintype "passive"))
      (node (ref "U2") (pin "5") (pinfunction "2IN+_5") (pintype "passive"))
    )
    (net (code "21") (name "Net-(R22-BOT)") (class "Default")
      (node (ref "C7") (pin "2") (pinfunction "2_2") (pintype "passive"))
      (node (ref "R22") (pin "2") (pinfunction "BOT_2") (pintype "passive"))
      (node (ref "R24") (pin "1") (pinfunction "TOP_1") (pintype "passive"))
      (node (ref "U2") (pin "6") (pinfunction "2IN-_6") (pintype "passive"))
    )
    (net (code "22") (name "Net-(R25-BOT)") (class "Default")
      (node (ref "R25") (pin "2") (pinfunction "BOT_2") (pintype "passive"))
      (node (ref "T3") (pin "1") (pinfunction "G_1") (pintype "passive"))
    )
    (net (code "23") (name "Net-(R25-TOP)") (class "Default")
      (node (ref "C10") (pin "1") (pinfunction "1_1") (pintype "passive"))
      (node (ref "R25") (pin "1") (pinfunction "TOP_1") (pintype "passive"))
      (node (ref "R28") (pin "2") (pinfunction "BOT_2") (pintype "passive"))
      (node (ref "U5") (pin "7") (pinfunction "2OUT_7") (pintype "passive"))
    )
    (net (code "24") (name "Net-(R26-BOT)") (class "Default")
      (node (ref "R26") (pin "2") (pinfunction "BOT_2") (pintype "passive"))
      (node (ref "T4") (pin "1") (pinfunction "G_1") (pintype "passive"))
    )
    (net (code "25") (name "Net-(R26-TOP)") (class "Default")
      (node (ref "C11") (pin "1") (pinfunction "1_1") (pintype "passive"))
      (node (ref "R26") (pin "1") (pinfunction "TOP_1") (pintype "passive"))
      (node (ref "R31") (pin "2") (pinfunction "BOT_2") (pintype "passive"))
      (node (ref "U5") (pin "1") (pinfunction "1OUT_1") (pintype "passive"))
    )
    (net (code "26") (name "Net-(R28-TOP)") (class "Default")
      (node (ref "C10") (pin "2") (pinfunction "2_2") (pintype "passive"))
      (node (ref "R28") (pin "1") (pinfunction "TOP_1") (pintype "passive"))
      (node (ref "R30") (pin "2") (pinfunction "BOT_2") (pintype "passive"))
      (node (ref "R32") (pin "2") (pinfunction "BOT_2") (pintype "passive"))
      (node (ref "U5") (pin "6") (pinfunction "2IN-_6") (pintype "passive"))
    )
    (net (code "27") (name "Net-(R30-TOP)") (class "Default")
      (node (ref "R30") (pin "1") (pinfunction "TOP_1") (pintype "passive"))
      (node (ref "R35") (pin "1") (pinfunction "TOP_1") (pintype "passive"))
      (node (ref "R37") (pin "1") (pinfunction "TOP_1") (pintype "passive"))
      (node (ref "R38") (pin "1") (pinfunction "TOP_1") (pintype "passive"))
      (node (ref "T3") (pin "3") (pinfunction "S_3") (pintype "passive"))
    )
    (net (code "28") (name "Net-(R31-TOP)") (class "Default")
      (node (ref "C11") (pin "2") (pinfunction "2_2") (pintype "passive"))
      (node (ref "R31") (pin "1") (pinfunction "TOP_1") (pintype "passive"))
      (node (ref "R33") (pin "2") (pinfunction "BOT_2") (pintype "passive"))
      (node (ref "R34") (pin "2") (pinfunction "BOT_2") (pintype "passive"))
      (node (ref "U5") (pin "2") (pinfunction "1IN-_2") (pintype "passive"))
    )
    (net (code "29") (name "Net-(R32-TOP)") (class "Default")
      (node (ref "C13") (pin "1") (pinfunction "1_1") (pintype "passive"))
      (node (ref "R32") (pin "1") (pinfunction "TOP_1") (pintype "passive"))
      (node (ref "R36") (pin "2") (pinfunction "BOT_2") (pintype "passive"))
      (node (ref "R46") (pin "2") (pinfunction "BOT_2") (pintype "passive"))
      (node (ref "TP8") (pin "1") (pinfunction "1_1") (pintype "passive"))
      (node (ref "U6") (pin "7") (pinfunction "2OUT_7") (pintype "passive"))
    )
    (net (code "30") (name "Net-(R33-TOP)") (class "Default")
      (node (ref "R33") (pin "1") (pinfunction "TOP_1") (pintype "passive"))
      (node (ref "R40") (pin "1") (pinfunction "TOP_1") (pintype "passive"))
      (node (ref "R42") (pin "1") (pinfunction "TOP_1") (pintype "passive"))
      (node (ref "R43") (pin "1") (pinfunction "TOP_1") (pintype "passive"))
      (node (ref "T4") (pin "3") (pinfunction "S_3") (pintype "passive"))
    )
    (net (code "31") (name "Net-(R34-TOP)") (class "Default")
      (node (ref "C14") (pin "1") (pinfunction "1_1") (pintype "passive"))
      (node (ref "R34") (pin "1") (pinfunction "TOP_1") (pintype "passive"))
      (node (ref "R41") (pin "2") (pinfunction "BOT_2") (pintype "passive"))
      (node (ref "R48") (pin "2") (pinfunction "BOT_2") (pintype "passive"))
      (node (ref "TP9") (pin "1") (pinfunction "1_1") (pintype "passive"))
      (node (ref "U6") (pin "1") (pinfunction "1OUT_1") (pintype "passive"))
    )
    (net (code "32") (name "Net-(R35-BOT)") (class "Default")
      (node (ref "R35") (pin "2") (pinfunction "BOT_2") (pintype "passive"))
      (node (ref "R45") (pin "1") (pinfunction "TOP_1") (pintype "passive"))
      (node (ref "U6") (pin "5") (pinfunction "2IN+_5") (pintype "passive"))
    )
    (net (code "33") (name "Net-(R39-BOT)") (class "Default")
      (node (ref "C13") (pin "2") (pinfunction "2_2") (pintype "passive"))
      (node (ref "R39") (pin "2") (pinfunction "BOT_2") (pintype "passive"))
      (node (ref "R46") (pin "1") (pinfunction "TOP_1") (pintype "passive"))
      (node (ref "U6") (pin "6") (pinfunction "2IN-_6") (pintype "passive"))
    )
    (net (code "34") (name "Net-(R40-BOT)") (class "Default")
      (node (ref "R40") (pin "2") (pinfunction "BOT_2") (pintype "passive"))
      (node (ref "R47") (pin "1") (pinfunction "TOP_1") (pintype "passive"))
      (node (ref "U6") (pin "3") (pinfunction "1IN+_3") (pintype "passive"))
    )
    (net (code "35") (name "Net-(R44-BOT)") (class "Default")
      (node (ref "C14") (pin "2") (pinfunction "2_2") (pintype "passive"))
      (node (ref "R44") (pin "2") (pinfunction "BOT_2") (pintype "passive"))
      (node (ref "R48") (pin "1") (pinfunction "TOP_1") (pintype "passive"))
      (node (ref "U6") (pin "2") (pinfunction "1IN-_2") (pintype "passive"))
    )
    (net (code "36") (name "Net-(R49-TOP)") (class "Default")
      (node (ref "R49") (pin "1") (pinfunction "TOP_1") (pintype "passive"))
      (node (ref "U3") (pin "1") (pinfunction "1OUT_1") (pintype "passive"))
      (node (ref "U3") (pin "2") (pinfunction "1IN-_2") (pintype "passive"))
    )
    (net (code "37") (name "VBUS") (class "Default")
      (node (ref "J2") (pin "2") (pinfunction "2_2") (pintype "passive"))
      (node (ref "M1") (pin "1") (pinfunction "1_1") (pintype "passive"))
      (node (ref "M1") (pin "2") (pinfunction "2_2") (pintype "passive"))
      (node (ref "M1") (pin "3") (pinfunction "3_3") (pintype "passive"))
      (node (ref "M1") (pin "4") (pinfunction "4_4") (pintype "passive"))
      (node (ref "M1") (pin "5") (pinfunction "5_5") (pintype "passive"))
      (node (ref "T1") (pin "2") (pinfunction "D_2") (pintype "passive"))
      (node (ref "T2") (pin "2") (pinfunction "D_2") (pintype "passive"))
      (node (ref "T3") (pin "2") (pinfunction "D_2") (pintype "passive"))
      (node (ref "T4") (pin "2") (pinfunction "D_2") (pintype "passive"))
    )
    (net (code "38") (name "VIN") (class "Default")
      (node (ref "J1") (pin "1") (pinfunction "1_1") (pintype "passive"))
    )
  )
)
